# Dreamcast.net
KiCad netlist of a schematic drawn in EAGLE
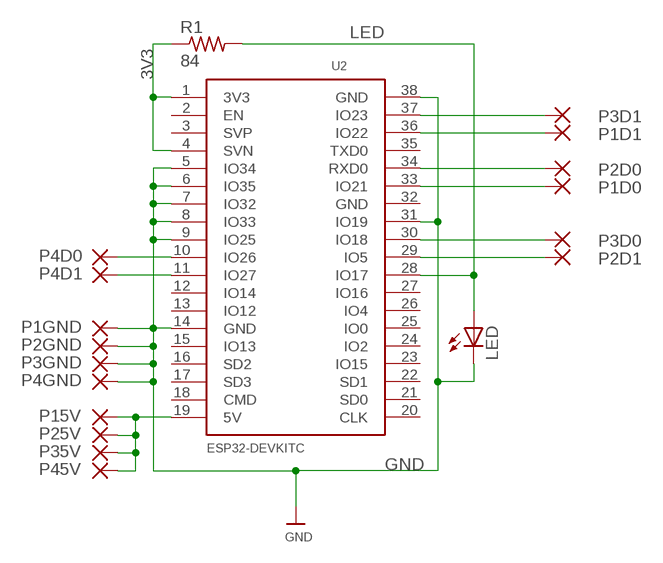
[diagram p0: schematic, sheet 1]

(export (version "E")
  (design (tool "Eeschema 10.0.6"))
  (components
    (comp (ref "LED")
      (value "LEDCHIPLED_1206")
      (footprint "eagle-import:CHIPLED_1206")
      (libsource (lib "eagle-import") (part "LEDCHIPLED_1206"))
    )
    (comp (ref "P1D0")
      (value "SMD5")
      (footprint "eagle-import:SMD2,54-5,08")
      (libsource (lib "eagle-import") (part "SMD5"))
    )
    (comp (ref "P1D1")
      (value "SMD5")
      (footprint "eagle-import:SMD2,54-5,08")
      (libsource (lib "eagle-import") (part "SMD5"))
    )
    (comp (ref "P1GND")
      (value "SMD5")
      (footprint "eagle-import:SMD2,54-5,08")
      (libsource (lib "eagle-import") (part "SMD5"))
    )
    (comp (ref "P2D0")
      (value "SMD5")
      (footprint "eagle-import:SMD2,54-5,08")
      (libsource (lib "eagle-import") (part "SMD5"))
    )
    (comp (ref "P2D1")
      (value "SMD5")
      (footprint "eagle-import:SMD2,54-5,08")
      (libsource (lib "eagle-import") (part "SMD5"))
    )
    (comp (ref "P2GND")
      (value "SMD5")
      (footprint "eagle-import:SMD2,54-5,08")
      (libsource (lib "eagle-import") (part "SMD5"))
    )
    (comp (ref "P3D0")
      (value "SMD5")
      (footprint "eagle-import:SMD2,54-5,08")
      (libsource (lib "eagle-import") (part "SMD5"))
    )
    (comp (ref "P3D1")
      (value "SMD5")
      (footprint "eagle-import:SMD2,54-5,08")
      (libsource (lib "eagle-import") (part "SMD5"))
    )
    (comp (ref "P3GND")
      (value "SMD5")
      (footprint "eagle-import:SMD2,54-5,08")
      (libsource (lib "eagle-import") (part "SMD5"))
    )
    (comp (ref "P4D0")
      (value "SMD5")
      (footprint "eagle-import:SMD2,54-5,08")
      (libsource (lib "eagle-import") (part "SMD5"))
    )
    (comp (ref "P4D1")
      (value "SMD5")
      (footprint "eagle-import:SMD2,54-5,08")
      (libsource (lib "eagle-import") (part "SMD5"))
    )
    (comp (ref "P4GND")
      (value "SMD5")
      (footprint "eagle-import:SMD2,54-5,08")
      (libsource (lib "eagle-import") (part "SMD5"))
    )
    (comp (ref "P15V")
      (value "SMD5")
      (footprint "eagle-import:SMD2,54-5,08")
      (libsource (lib "eagle-import") (part "SMD5"))
    )
    (comp (ref "P25V")
      (value "SMD5")
      (footprint "eagle-import:SMD2,54-5,08")
      (libsource (lib "eagle-import") (part "SMD5"))
    )
    (comp (ref "P35V")
      (value "SMD5")
      (footprint "eagle-import:SMD2,54-5,08")
      (libsource (lib "eagle-import") (part "SMD5"))
    )
    (comp (ref "P45V")
      (value "SMD5")
      (footprint "eagle-import:SMD2,54-5,08")
      (libsource (lib "eagle-import") (part "SMD5"))
    )
    (comp (ref "R1")
      (value "84")
      (footprint "eagle-import:R1206")
      (libsource (lib "eagle-import") (part "R-US_R1206"))
    )
    (comp (ref "U2")
      (value "ESP32DEVKITC")
      (footprint "eagle-import:ESP32-DEVKITC")
      (libsource (lib "eagle-import") (part "ESP32DEVKITC"))
    )
  )
  (nets
    (net (code "1") (name "/3V3") (class "Default")
      (node (ref "R1") (pin "1") (pinfunction "1_1") (pintype "passive"))
      (node (ref "U2") (pin "1") (pinfunction "3V3_1") (pintype "bidirectional"))
      (node (ref "U2") (pin "4") (pinfunction "SVN_4") (pintype "bidirectional"))
    )
    (net (code "2") (name "/LED") (class "Default")
      (node (ref "LED") (pin "A") (pinfunction "A_A") (pintype "passive"))
      (node (ref "R1") (pin "2") (pinfunction "2_2") (pintype "passive"))
      (node (ref "U2") (pin "28") (pinfunction "IO17_28") (pintype "bidirectional"))
    )
    (net (code "3") (name "GND") (class "Default")
      (node (ref "LED") (pin "C") (pinfunction "C_C") (pintype "passive"))
      (node (ref "P1GND") (pin "1") (pinfunction "P_1") (pintype "passive"))
      (node (ref "P2GND") (pin "1") (pinfunction "P_1") (pintype "passive"))
      (node (ref "P3GND") (pin "1") (pinfunction "P_1") (pintype "passive"))
      (node (ref "P4GND") (pin "1") (pinfunction "P_1") (pintype "passive"))
      (node (ref "U2") (pin "14") (pinfunction "GND_14") (pintype "bidirectional"))
      (node (ref "U2") (pin "31") (pinfunction "IO19_31") (pintype "bidirectional"))
      (node (ref "U2") (pin "38") (pinfunction "GND_38") (pintype "bidirectional"))
      (node (ref "U2") (pin "5") (pinfunction "IO34_5") (pintype "bidirectional"))
      (node (ref "U2") (pin "6") (pinfunction "IO35_6") (pintype "bidirectional"))
      (node (ref "U2") (pin "7") (pinfunction "IO32_7") (pintype "bidirectional"))
      (node (ref "U2") (pin "8") (pinfunction "IO33_8") (pintype "bidirectional"))
      (node (ref "U2") (pin "9") (pinfunction "IO25_9") (pintype "bidirectional"))
    )
    (net (code "4") (name "Net-(P1D0-P)") (class "Default")
      (node (ref "P1D0") (pin "1") (pinfunction "P_1") (pintype "passive"))
      (node (ref "U2") (pin "33") (pinfunction "IO21_33") (pintype "bidirectional"))
    )
    (net (code "5") (name "Net-(P1D1-P)") (class "Default")
      (node (ref "P1D1") (pin "1") (pinfunction "P_1") (pintype "passive"))
      (node (ref "U2") (pin "36") (pinfunction "IO22_36") (pintype "bidirectional"))
    )
    (net (code "6") (name "Net-(P2D0-P)") (class "Default")
      (node (ref "P2D0") (pin "1") (pinfunction "P_1") (pintype "passive"))
      (node (ref "U2") (pin "34") (pinfunction "RXD0_34") (pintype "bidirectional"))
    )
    (net (code "7") (name "Net-(P2D1-P)") (class "Default")
      (node (ref "P2D1") (pin "1") (pinfunction "P_1") (pintype "passive"))
      (node (ref "U2") (pin "29") (pinfunction "IO5_29") (pintype "bidirectional"))
    )
    (net (code "8") (name "Net-(P3D0-P)") (class "Default")
      (node (ref "P3D0") (pin "1") (pinfunction "P_1") (pintype "passive"))
      (node (ref "U2") (pin "30") (pinfunction "IO18_30") (pintype "bidirectional"))
    )
    (net (code "9") (name "Net-(P3D1-P)") (class "Default")
      (node (ref "P3D1") (pin "1") (pinfunction "P_1") (pintype "passive"))
      (node (ref "U2") (pin "37") (pinfunction "IO23_37") (pintype "bidirectional"))
    )
    (net (code "10") (name "Net-(P4D0-P)") (class "Default")
      (node (ref "P4D0") (pin "1") (pinfunction "P_1") (pintype "passive"))
      (node (ref "U2") (pin "10") (pinfunction "IO26_10") (pintype "bidirectional"))
    )
    (net (code "11") (name "Net-(P4D1-P)") (class "Default")
      (node (ref "P4D1") (pin "1") (pinfunction "P_1") (pintype "passive"))
      (node (ref "U2") (pin "11") (pinfunction "IO27_11") (pintype "bidirectional"))
    )
    (net (code "12") (name "Net-(P15V-P)") (class "Default")
      (node (ref "P15V") (pin "1") (pinfunction "P_1") (pintype "passive"))
      (node (ref "P25V") (pin "1") (pinfunction "P_1") (pintype "passive"))
      (node (ref "P35V") (pin "1") (pinfunction "P_1") (pintype "passive"))
      (node (ref "P45V") (pin "1") (pinfunction "P_1") (pintype "passive"))
      (node (ref "U2") (pin "19") (pinfunction "5V_19") (pintype "bidirectional"))
    )
    (net (code "13") (name "unconnected-(U2-CLK-Pad20)") (class "Default")
      (node (ref "U2") (pin "20") (pinfunction "CLK_20") (pintype "bidirectional"))
    )
    (net (code "14") (name "unconnected-(U2-CMD-Pad18)") (class "Default")
      (node (ref "U2") (pin "18") (pinfunction "CMD_18") (pintype "bidirectional"))
    )
    (net (code "15") (name "unconnected-(U2-EN-Pad2)") (class "Default")
      (node (ref "U2") (pin "2") (pinfunction "EN_2") (pintype "bidirectional"))
    )
    (net (code "16") (name "unconnected-(U2-GND-Pad32)") (class "Default")
      (node (ref "U2") (pin "32") (pinfunction "GND_32") (pintype "bidirectional"))
    )
    (net (code "17") (name "unconnected-(U2-IO0-Pad25)") (class "Default")
      (node (ref "U2") (pin "25") (pinfunction "IO0_25") (pintype "bidirectional"))
    )
    (net (code "18") (name "unconnected-(U2-IO2-Pad24)") (class "Default")
      (node (ref "U2") (pin "24") (pinfunction "IO2_24") (pintype "bidirectional"))
    )
    (net (code "19") (name "unconnected-(U2-IO4-Pad26)") (class "Default")
      (node (ref "U2") (pin "26") (pinfunction "IO4_26") (pintype "bidirectional"))
    )
    (net (code "20") (name "unconnected-(U2-IO12-Pad13)") (class "Default")
      (node (ref "U2") (pin "13") (pinfunction "IO12_13") (pintype "bidirectional"))
    )
    (net (code "21") (name "unconnected-(U2-IO13-Pad15)") (class "Default")
      (node (ref "U2") (pin "15") (pinfunction "IO13_15") (pintype "bidirectional"))
    )
    (net (code "22") (name "unconnected-(U2-IO14-Pad12)") (class "Default")
      (node (ref "U2") (pin "12") (pinfunction "IO14_12") (pintype "bidirectional"))
    )
    (net (code "23") (name "unconnected-(U2-IO15-Pad23)") (class "Default")
      (node (ref "U2") (pin "23") (pinfunction "IO15_23") (pintype "bidirectional"))
    )
    (net (code "24") (name "unconnected-(U2-IO16-Pad27)") (class "Default")
      (node (ref "U2") (pin "27") (pinfunction "IO16_27") (pintype "bidirectional"))
    )
    (net (code "25") (name "unconnected-(U2-SD0-Pad21)") (class "Default")
      (node (ref "U2") (pin "21") (pinfunction "SD0_21") (pintype "bidirectional"))
    )
    (net (code "26") (name "unconnected-(U2-SD1-Pad22)") (class "Default")
      (node (ref "U2") (pin "22") (pinfunction "SD1_22") (pintype "bidirectional"))
    )
    (net (code "27") (name "unconnected-(U2-SD2-Pad16)") (class "Default")
      (node (ref "U2") (pin "16") (pinfunction "SD2_16") (pintype "bidirectional"))
    )
    (net (code "28") (name "unconnected-(U2-SD3-Pad17)") (class "Default")
      (node (ref "U2") (pin "17") (pinfunction "SD3_17") (pintype "bidirectional"))
    )
    (net (code "29") (name "unconnected-(U2-SVP-Pad3)") (class "Default")
      (node (ref "U2") (pin "3") (pinfunction "SVP_3") (pintype "bidirectional"))
    )
    (net (code "30") (name "unconnected-(U2-TXD0-Pad35)") (class "Default")
      (node (ref "U2") (pin "35") (pinfunction "TXD0_35") (pintype "bidirectional"))
    )
  )
)
